# power_and_clocks.net
KiCad netlist of a schematic drawn in Altium Designer
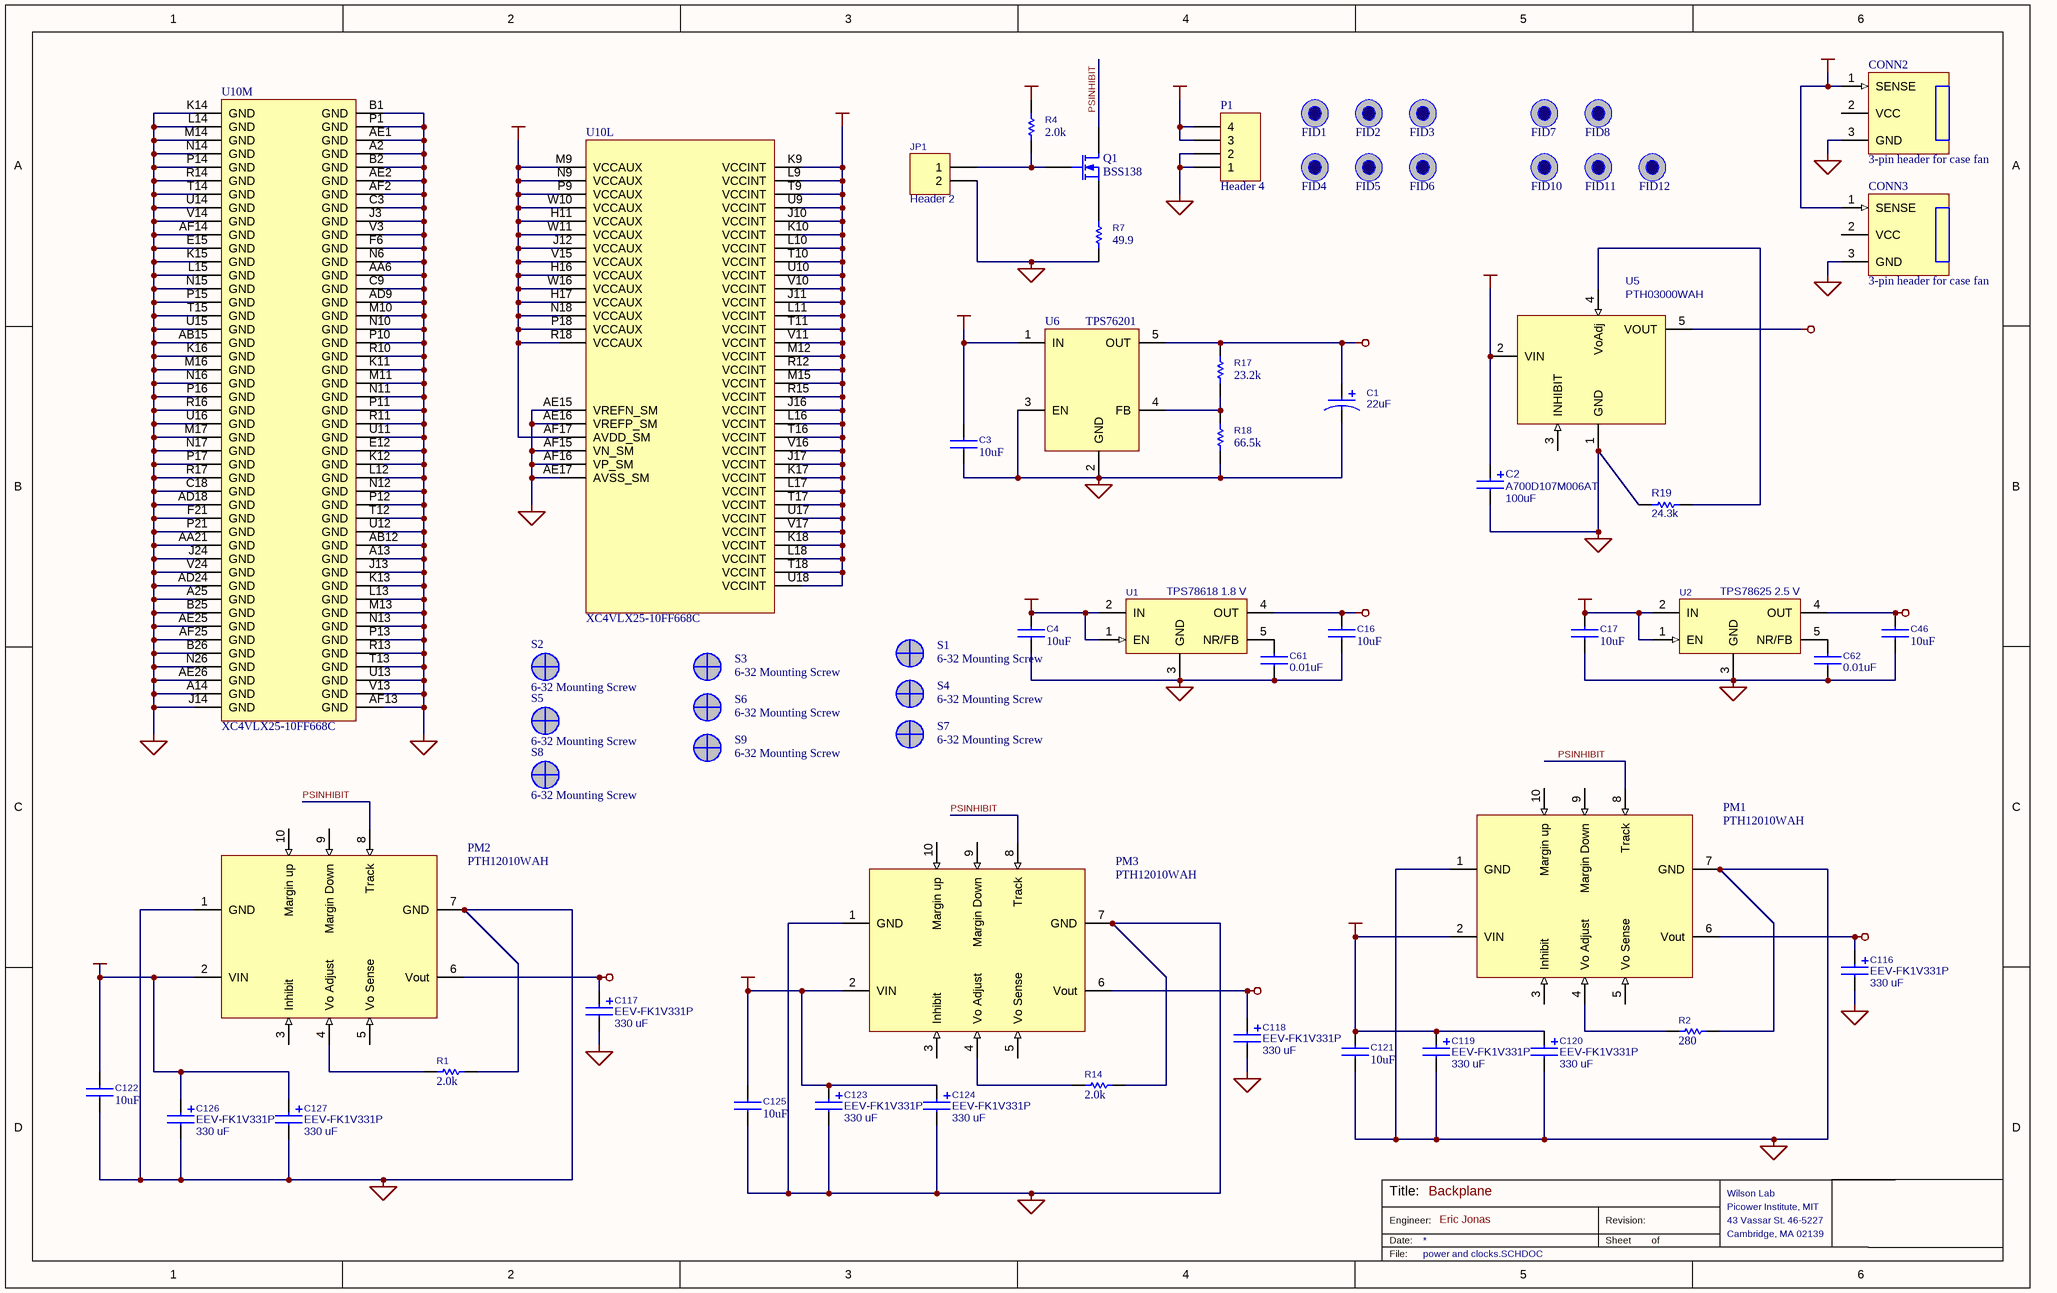
[diagram p0: power and clocks.SCHDOC]

(export (version "E")
  (design (tool "Eeschema 10.0.6"))
  (components
    (comp (ref "C1")
      (value "22uF")
      (footprint "6032")
      (description "Standard Capacitor")
      (fields (field (name "Comment") "POLCAP2"))
      (libsource (lib "parts") (part "POLCAP2"))
    )
    (comp (ref "C2")
      (value "A700D107M006AT")
      (footprint "7343")
      (description "Standard Capacitor")
      (fields (field (name "ALTIUM_VALUE") "100uF"))
      (libsource (lib "parts") (part "POLCAP"))
    )
    (comp (ref "C3")
      (value "10uF")
      (footprint "1206")
      (description "Standard Capacitor")
      (libsource (lib "parts") (part "CAPACITOR"))
    )
    (comp (ref "C4")
      (value "10uF")
      (footprint "1206")
      (description "Standard Capacitor")
      (libsource (lib "parts") (part "CAPACITOR"))
    )
    (comp (ref "C16")
      (value "10uF")
      (footprint "1206")
      (description "Standard Capacitor")
      (libsource (lib "parts") (part "CAPACITOR"))
    )
    (comp (ref "C17")
      (value "10uF")
      (footprint "1206")
      (description "Standard Capacitor")
      (libsource (lib "parts") (part "CAPACITOR"))
    )
    (comp (ref "C46")
      (value "10uF")
      (footprint "1206")
      (description "Standard Capacitor")
      (libsource (lib "parts") (part "CAPACITOR"))
    )
    (comp (ref "C61")
      (value "0.01uF")
      (footprint "0402")
      (description "Standard Capacitor")
      (fields (field (name "Comment") "CAPACITOR"))
      (libsource (lib "parts") (part "CAPACITOR"))
    )
    (comp (ref "C62")
      (value "0.01uF")
      (footprint "0402")
      (description "Standard Capacitor")
      (fields (field (name "Comment") "CAPACITOR"))
      (libsource (lib "parts") (part "CAPACITOR"))
    )
    (comp (ref "C116")
      (value "EEV-FK1V331P")
      (footprint "PanasonicG")
      (description "Standard Capacitor")
      (fields (field (name "ALTIUM_VALUE") "330 uF"))
      (libsource (lib "parts") (part "POLCAP"))
    )
    (comp (ref "C117")
      (value "EEV-FK1V331P")
      (footprint "PanasonicG")
      (description "Standard Capacitor")
      (fields (field (name "ALTIUM_VALUE") "330 uF"))
      (libsource (lib "parts") (part "POLCAP"))
    )
    (comp (ref "C118")
      (value "EEV-FK1V331P")
      (footprint "PanasonicG")
      (description "Standard Capacitor")
      (fields (field (name "ALTIUM_VALUE") "330 uF"))
      (libsource (lib "parts") (part "POLCAP"))
    )
    (comp (ref "C119")
      (value "EEV-FK1V331P")
      (footprint "PanasonicG")
      (description "Standard Capacitor")
      (fields (field (name "ALTIUM_VALUE") "330 uF"))
      (libsource (lib "parts") (part "POLCAP"))
    )
    (comp (ref "C120")
      (value "EEV-FK1V331P")
      (footprint "PanasonicG")
      (description "Standard Capacitor")
      (fields (field (name "ALTIUM_VALUE") "330 uF"))
      (libsource (lib "parts") (part "POLCAP"))
    )
    (comp (ref "C121")
      (value "10uF")
      (footprint "1206")
      (description "Standard Capacitor")
      (libsource (lib "parts") (part "CAPACITOR"))
    )
    (comp (ref "C122")
      (value "10uF")
      (footprint "1206")
      (description "Standard Capacitor")
      (libsource (lib "parts") (part "CAPACITOR"))
    )
    (comp (ref "C123")
      (value "EEV-FK1V331P")
      (footprint "PanasonicG")
      (description "Standard Capacitor")
      (fields (field (name "ALTIUM_VALUE") "330 uF"))
      (libsource (lib "parts") (part "POLCAP"))
    )
    (comp (ref "C124")
      (value "EEV-FK1V331P")
      (footprint "PanasonicG")
      (description "Standard Capacitor")
      (fields (field (name "ALTIUM_VALUE") "330 uF"))
      (libsource (lib "parts") (part "POLCAP"))
    )
    (comp (ref "C125")
      (value "10uF")
      (footprint "1206")
      (description "Standard Capacitor")
      (libsource (lib "parts") (part "CAPACITOR"))
    )
    (comp (ref "C126")
      (value "EEV-FK1V331P")
      (footprint "PanasonicG")
      (description "Standard Capacitor")
      (fields (field (name "ALTIUM_VALUE") "330 uF"))
      (libsource (lib "parts") (part "POLCAP"))
    )
    (comp (ref "C127")
      (value "EEV-FK1V331P")
      (footprint "PanasonicG")
      (description "Standard Capacitor")
      (fields (field (name "ALTIUM_VALUE") "330 uF"))
      (libsource (lib "parts") (part "POLCAP"))
    )
    (comp (ref "CONN2")
      (value "3-pin header for case fan")
      (footprint "CASEFANHDR")
      (libsource (lib "parts") (part "PCFANHEADER"))
    )
    (comp (ref "CONN3")
      (value "3-pin header for case fan")
      (footprint "CASEFANHDR")
      (libsource (lib "parts") (part "PCFANHEADER"))
    )
    (comp (ref "FID1")
      (value "FIDUCIAL")
      (footprint "FIDUCIAL")
      (description "Fiducial")
      (libsource (lib "parts") (part "FIDUCIAL"))
    )
    (comp (ref "FID2")
      (value "FIDUCIAL")
      (footprint "FIDUCIAL")
      (description "Fiducial")
      (libsource (lib "parts") (part "FIDUCIAL"))
    )
    (comp (ref "FID3")
      (value "FIDUCIAL")
      (footprint "FIDUCIAL")
      (description "Fiducial")
      (libsource (lib "parts") (part "FIDUCIAL"))
    )
    (comp (ref "FID4")
      (value "FIDUCIAL")
      (footprint "FIDUCIAL")
      (description "Fiducial")
      (libsource (lib "parts") (part "FIDUCIAL"))
    )
    (comp (ref "FID5")
      (value "FIDUCIAL")
      (footprint "FIDUCIAL")
      (description "Fiducial")
      (libsource (lib "parts") (part "FIDUCIAL"))
    )
    (comp (ref "FID6")
      (value "FIDUCIAL")
      (footprint "FIDUCIAL")
      (description "Fiducial")
      (libsource (lib "parts") (part "FIDUCIAL"))
    )
    (comp (ref "FID7")
      (value "FIDUCIAL")
      (footprint "FIDUCIAL")
      (description "Fiducial")
      (libsource (lib "parts") (part "FIDUCIAL"))
    )
    (comp (ref "FID8")
      (value "FIDUCIAL")
      (footprint "FIDUCIAL")
      (description "Fiducial")
      (libsource (lib "parts") (part "FIDUCIAL"))
    )
    (comp (ref "FID10")
      (value "FIDUCIAL")
      (footprint "FIDUCIAL")
      (description "Fiducial")
      (libsource (lib "parts") (part "FIDUCIAL"))
    )
    (comp (ref "FID11")
      (value "FIDUCIAL")
      (footprint "FIDUCIAL")
      (description "Fiducial")
      (libsource (lib "parts") (part "FIDUCIAL"))
    )
    (comp (ref "FID12")
      (value "FIDUCIAL")
      (footprint "FIDUCIAL")
      (description "Fiducial")
      (libsource (lib "parts") (part "FIDUCIAL"))
    )
    (comp (ref "JP1")
      (value "Header 2")
      (footprint "HDR1X2")
      (description "Header, 2-Pin")
      (fields (field (name "MANUFACTURER") "Generic Components") (field (name "PUBLISHER") "Altium Limited"))
      (libsource (lib "Miscellaneous Connectors") (part "Header 2"))
    )
    (comp (ref "P1")
      (value "Header 4")
      (footprint "MOLEX 39-29-9042")
      (description "Header, 4-Pin")
      (fields (field (name "PUBLISHER") "Altium Limited"))
      (libsource (lib "Miscellaneous Connectors") (part "Header 4"))
    )
    (comp (ref "PM1")
      (value "PTH12010WAH")
      (footprint "PTH12010WAH")
      (description "12A 12V Input Non-isolated wide-output adj")
      (libsource (lib "parts") (part "PTH12010W"))
    )
    (comp (ref "PM2")
      (value "PTH12010WAH")
      (footprint "PTH12010WAH")
      (description "12A 12V Input Non-isolated wide-output adj")
      (libsource (lib "parts") (part "PTH12010W"))
    )
    (comp (ref "PM3")
      (value "PTH12010WAH")
      (footprint "PTH12010WAH")
      (description "12A 12V Input Non-isolated wide-output adj")
      (libsource (lib "parts") (part "PTH12010W"))
    )
    (comp (ref "Q1") (value "BSS138") (footprint "SO-G3/D4.1") (libsource (lib "parts") (part "BSS138")))
    (comp (ref "R1")
      (value "2.0k")
      (footprint "1206")
      (description "Standard Passive Resistor")
      (fields (field (name "TOLERANCE") "1%"))
      (libsource (lib "parts") (part "RESISTOR"))
    )
    (comp (ref "R2")
      (value "280")
      (footprint "1206")
      (description "Standard Passive Resistor")
      (fields (field (name "TOLERANCE") "1%"))
      (libsource (lib "parts") (part "RESISTOR"))
    )
    (comp (ref "R4")
      (value "2.0k")
      (footprint "1206")
      (description "Standard Passive Resistor")
      (fields (field (name "TOLERANCE") "1%") (field (name "Comment") "5k"))
      (libsource (lib "parts") (part "RESISTOR"))
    )
    (comp (ref "R7")
      (value "49.9")
      (footprint "1206")
      (description "Standard Passive Resistor")
      (fields (field (name "TOLERANCE") "1%") (field (name "Comment") "50"))
      (libsource (lib "parts") (part "RESISTOR"))
    )
    (comp (ref "R14")
      (value "2.0k")
      (footprint "1206")
      (description "Standard Passive Resistor")
      (fields (field (name "TOLERANCE") "1%"))
      (libsource (lib "parts") (part "RESISTOR"))
    )
    (comp (ref "R17")
      (value "23.2k")
      (footprint "1206")
      (description "Standard Passive Resistor")
      (fields (field (name "TOLERANCE") "1%"))
      (libsource (lib "parts") (part "RESISTOR"))
    )
    (comp (ref "R18")
      (value "66.5k")
      (footprint "1206")
      (description "Standard Passive Resistor")
      (fields (field (name "TOLERANCE") "1%"))
      (libsource (lib "parts") (part "RESISTOR"))
    )
    (comp (ref "R19")
      (value "24.3k")
      (footprint "1206")
      (description "Standard Passive Resistor")
      (fields (field (name "TOLERANCE") "1%") (field (name "Comment") "RESISTOR"))
      (libsource (lib "parts") (part "RESISTOR"))
    )
    (comp (ref "S1")
      (value "6-32 Mounting Screw")
      (footprint "SCREW6-32")
      (libsource (lib "parts") (part "MNTSCREW"))
    )
    (comp (ref "S2")
      (value "6-32 Mounting Screw")
      (footprint "SCREW6-32")
      (libsource (lib "parts") (part "MNTSCREW"))
    )
    (comp (ref "S3")
      (value "6-32 Mounting Screw")
      (footprint "SCREW6-32")
      (libsource (lib "parts") (part "MNTSCREW"))
    )
    (comp (ref "S4")
      (value "6-32 Mounting Screw")
      (footprint "SCREW6-32")
      (libsource (lib "parts") (part "MNTSCREW"))
    )
    (comp (ref "S5")
      (value "6-32 Mounting Screw")
      (footprint "SCREW6-32")
      (libsource (lib "parts") (part "MNTSCREW"))
    )
    (comp (ref "S6")
      (value "6-32 Mounting Screw")
      (footprint "SCREW6-32")
      (libsource (lib "parts") (part "MNTSCREW"))
    )
    (comp (ref "S7")
      (value "6-32 Mounting Screw")
      (footprint "SCREW6-32")
      (libsource (lib "parts") (part "MNTSCREW"))
    )
    (comp (ref "S8")
      (value "6-32 Mounting Screw")
      (footprint "SCREW6-32")
      (libsource (lib "parts") (part "MNTSCREW"))
    )
    (comp (ref "S9")
      (value "6-32 Mounting Screw")
      (footprint "SCREW6-32")
      (libsource (lib "parts") (part "MNTSCREW"))
    )
    (comp (ref "U1")
      (value "TPS78618 1.8 V")
      (footprint "KTT")
      (description "TI 1.5A LDO")
      (libsource (lib "parts") (part "TPS768XX"))
    )
    (comp (ref "U2")
      (value "TPS78625 2.5 V")
      (footprint "KTT")
      (description "TI 1.5A LDO")
      (libsource (lib "parts") (part "TPS786XX"))
    )
    (comp (ref "U5") (value "PTH03000WAH") (footprint "TI EUS") (libsource (lib "parts") (part "PTH03000")))
    (comp (ref "U6")
      (value "TPS76201")
      (footprint "SO-G5/X.5")
      (description "TI 100mA LDO")
      (libsource (lib "parts") (part "TSP76201"))
    )
    (comp (ref "U10")
      (value "XC4VLX25-10FF668C")
      (footprint "Xilinx FF668")
      (description "Xilinx Virtex-4")
      (libsource (lib "parts") (part "XC4VLX25-10FF668C"))
    )
  )
  (nets
    (net (code "1") (name "+0.9VCC") (class "Default")
      (node (ref "C1") (pin "1") (pintype "passive"))
      (node (ref "R17") (pin "1") (pintype "passive"))
      (node (ref "U6") (pin "5") (pinfunction "OUT_5") (pintype "power_in"))
    )
    (net (code "2") (name "+1.2VCC") (class "Default")
      (node (ref "U10") (pin "J10") (pinfunction "VCCINT_J10") (pintype "power_in"))
      (node (ref "U10") (pin "J11") (pinfunction "VCCINT_J11") (pintype "power_in"))
      (node (ref "U10") (pin "J16") (pinfunction "VCCINT_J16") (pintype "power_in"))
      (node (ref "U10") (pin "J17") (pinfunction "VCCINT_J17") (pintype "power_in"))
      (node (ref "U10") (pin "K10") (pinfunction "VCCINT_K10") (pintype "power_in"))
      (node (ref "U10") (pin "K17") (pinfunction "VCCINT_K17") (pintype "power_in"))
      (node (ref "U10") (pin "K18") (pinfunction "VCCINT_K18") (pintype "power_in"))
      (node (ref "U10") (pin "K9") (pinfunction "VCCINT_K9") (pintype "power_in"))
      (node (ref "U10") (pin "L10") (pinfunction "VCCINT_L10") (pintype "power_in"))
      (node (ref "U10") (pin "L11") (pinfunction "VCCINT_L11") (pintype "power_in"))
      (node (ref "U10") (pin "L16") (pinfunction "VCCINT_L16") (pintype "power_in"))
      (node (ref "U10") (pin "L17") (pinfunction "VCCINT_L17") (pintype "power_in"))
      (node (ref "U10") (pin "L18") (pinfunction "VCCINT_L18") (pintype "power_in"))
      (node (ref "U10") (pin "L9") (pinfunction "VCCINT_L9") (pintype "power_in"))
      (node (ref "U10") (pin "M12") (pinfunction "VCCINT_M12") (pintype "power_in"))
      (node (ref "U10") (pin "M15") (pinfunction "VCCINT_M15") (pintype "power_in"))
      (node (ref "U10") (pin "R12") (pinfunction "VCCINT_R12") (pintype "power_in"))
      (node (ref "U10") (pin "R15") (pinfunction "VCCINT_R15") (pintype "power_in"))
      (node (ref "U10") (pin "T10") (pinfunction "VCCINT_T10") (pintype "power_in"))
      (node (ref "U10") (pin "T11") (pinfunction "VCCINT_T11") (pintype "power_in"))
      (node (ref "U10") (pin "T16") (pinfunction "VCCINT_T16") (pintype "power_in"))
      (node (ref "U10") (pin "T17") (pinfunction "VCCINT_T17") (pintype "power_in"))
      (node (ref "U10") (pin "T18") (pinfunction "VCCINT_T18") (pintype "power_in"))
      (node (ref "U10") (pin "T9") (pinfunction "VCCINT_T9") (pintype "power_in"))
      (node (ref "U10") (pin "U10") (pinfunction "VCCINT_U10") (pintype "power_in"))
      (node (ref "U10") (pin "U17") (pinfunction "VCCINT_U17") (pintype "power_in"))
      (node (ref "U10") (pin "U18") (pinfunction "VCCINT_U18") (pintype "power_in"))
      (node (ref "U10") (pin "U9") (pinfunction "VCCINT_U9") (pintype "power_in"))
      (node (ref "U10") (pin "V10") (pinfunction "VCCINT_V10") (pintype "power_in"))
      (node (ref "U10") (pin "V11") (pinfunction "VCCINT_V11") (pintype "power_in"))
      (node (ref "U10") (pin "V16") (pinfunction "VCCINT_V16") (pintype "power_in"))
      (node (ref "U10") (pin "V17") (pinfunction "VCCINT_V17") (pintype "power_in"))
      (node (ref "U5") (pin "5") (pinfunction "VOUT_5") (pintype "power_in"))
    )
    (net (code "3") (name "+1.8VCC") (class "Default")
      (node (ref "C16") (pin "2") (pintype "passive"))
      (node (ref "U1") (pin "4") (pinfunction "OUT_4") (pintype "power_in"))
    )
    (net (code "4") (name "+2.5VCC") (class "Default")
      (node (ref "C46") (pin "2") (pintype "passive"))
      (node (ref "U10") (pin "AF17") (pinfunction "AVDD_SM_AF17") (pintype "power_in"))
      (node (ref "U10") (pin "H11") (pinfunction "VCCAUX_H11") (pintype "power_in"))
      (node (ref "U10") (pin "H16") (pinfunction "VCCAUX_H16") (pintype "power_in"))
      (node (ref "U10") (pin "H17") (pinfunction "VCCAUX_H17") (pintype "power_in"))
      (node (ref "U10") (pin "J12") (pinfunction "VCCAUX_J12") (pintype "power_in"))
      (node (ref "U10") (pin "M9") (pinfunction "VCCAUX_M9") (pintype "power_in"))
      (node (ref "U10") (pin "N18") (pinfunction "VCCAUX_N18") (pintype "power_in"))
      (node (ref "U10") (pin "N9") (pinfunction "VCCAUX_N9") (pintype "power_in"))
      (node (ref "U10") (pin "P18") (pinfunction "VCCAUX_P18") (pintype "power_in"))
      (node (ref "U10") (pin "P9") (pinfunction "VCCAUX_P9") (pintype "power_in"))
      (node (ref "U10") (pin "R18") (pinfunction "VCCAUX_R18") (pintype "power_in"))
      (node (ref "U10") (pin "V15") (pinfunction "VCCAUX_V15") (pintype "power_in"))
      (node (ref "U10") (pin "W10") (pinfunction "VCCAUX_W10") (pintype "power_in"))
      (node (ref "U10") (pin "W11") (pinfunction "VCCAUX_W11") (pintype "power_in"))
      (node (ref "U10") (pin "W16") (pinfunction "VCCAUX_W16") (pintype "power_in"))
      (node (ref "U2") (pin "4") (pinfunction "OUT_4") (pintype "power_in"))
    )
    (net (code "5") (name "+5VCC") (class "Default")
      (node (ref "C116") (pin "1") (pintype "passive"))
      (node (ref "PM1") (pin "6") (pinfunction "Vout_6") (pintype "power_in"))
    )
    (net (code "6") (name "+12VCC") (class "Default")
      (node (ref "C119") (pin "1") (pintype "passive"))
      (node (ref "C120") (pin "1") (pintype "passive"))
      (node (ref "C121") (pin "2") (pintype "passive"))
      (node (ref "C122") (pin "2") (pintype "passive"))
      (node (ref "C123") (pin "1") (pintype "passive"))
      (node (ref "C124") (pin "1") (pintype "passive"))
      (node (ref "C125") (pin "2") (pintype "passive"))
      (node (ref "C126") (pin "1") (pintype "passive"))
      (node (ref "C127") (pin "1") (pintype "passive"))
      (node (ref "CONN2") (pin "1") (pinfunction "SENSE_1") (pintype "input"))
      (node (ref "CONN3") (pin "1") (pinfunction "SENSE_1") (pintype "input"))
      (node (ref "P1") (pin "3") (pinfunction "3_3") (pintype "passive"))
      (node (ref "P1") (pin "4") (pinfunction "4_4") (pintype "passive"))
      (node (ref "PM1") (pin "2") (pinfunction "VIN_2") (pintype "power_in"))
      (node (ref "PM2") (pin "2") (pinfunction "VIN_2") (pintype "power_in"))
      (node (ref "PM3") (pin "2") (pinfunction "VIN_2") (pintype "power_in"))
    )
    (net (code "7") (name "/PSINHIBIT") (class "Default")
      (node (ref "PM1") (pin "8") (pinfunction "Track_8") (pintype "input"))
      (node (ref "PM2") (pin "8") (pinfunction "Track_8") (pintype "input"))
      (node (ref "PM3") (pin "8") (pinfunction "Track_8") (pintype "input"))
      (node (ref "Q1") (pin "1") (pinfunction "D_1") (pintype "passive"))
    )
    (net (code "8") (name "GND") (class "Default")
      (node (ref "C1") (pin "2") (pintype "passive"))
      (node (ref "C116") (pin "2") (pintype "passive"))
      (node (ref "C117") (pin "2") (pintype "passive"))
      (node (ref "C118") (pin "2") (pintype "passive"))
      (node (ref "C119") (pin "2") (pintype "passive"))
      (node (ref "C120") (pin "2") (pintype "passive"))
      (node (ref "C121") (pin "1") (pintype "passive"))
      (node (ref "C122") (pin "1") (pintype "passive"))
      (node (ref "C123") (pin "2") (pintype "passive"))
      (node (ref "C124") (pin "2") (pintype "passive"))
      (node (ref "C125") (pin "1") (pintype "passive"))
      (node (ref "C126") (pin "2") (pintype "passive"))
      (node (ref "C127") (pin "2") (pintype "passive"))
      (node (ref "C16") (pin "1") (pintype "passive"))
      (node (ref "C17") (pin "1") (pintype "passive"))
      (node (ref "C2") (pin "2") (pintype "passive"))
      (node (ref "C3") (pin "1") (pintype "passive"))
      (node (ref "C4") (pin "1") (pintype "passive"))
      (node (ref "C46") (pin "1") (pintype "passive"))
      (node (ref "C61") (pin "2") (pintype "passive"))
      (node (ref "C62") (pin "2") (pintype "passive"))
      (node (ref "CONN2") (pin "3") (pinfunction "GND_3") (pintype "power_in"))
      (node (ref "CONN3") (pin "3") (pinfunction "GND_3") (pintype "power_in"))
      (node (ref "JP1") (pin "2") (pinfunction "2_2") (pintype "passive"))
      (node (ref "P1") (pin "1") (pinfunction "1_1") (pintype "passive"))
      (node (ref "P1") (pin "2") (pinfunction "2_2") (pintype "passive"))
      (node (ref "PM1") (pin "1") (pinfunction "GND_1") (pintype "power_in"))
      (node (ref "PM1") (pin "7") (pinfunction "GND_7") (pintype "power_in"))
      (node (ref "PM2") (pin "1") (pinfunction "GND_1") (pintype "power_in"))
      (node (ref "PM2") (pin "7") (pinfunction "GND_7") (pintype "power_in"))
      (node (ref "PM3") (pin "1") (pinfunction "GND_1") (pintype "power_in"))
      (node (ref "PM3") (pin "7") (pinfunction "GND_7") (pintype "power_in"))
      (node (ref "R1") (pin "1") (pintype "passive"))
      (node (ref "R14") (pin "1") (pintype "passive"))
      (node (ref "R18") (pin "2") (pintype "passive"))
      (node (ref "R19") (pin "2") (pintype "passive"))
      (node (ref "R2") (pin "1") (pintype "passive"))
      (node (ref "R7") (pin "2") (pintype "passive"))
      (node (ref "U1") (pin "3") (pinfunction "GND_3") (pintype "power_in"))
      (node (ref "U10") (pin "A13") (pinfunction "GND_A13") (pintype "power_in"))
      (node (ref "U10") (pin "A14") (pinfunction "GND_A14") (pintype "power_in"))
      (node (ref "U10") (pin "A2") (pinfunction "GND_A2") (pintype "power_in"))
      (node (ref "U10") (pin "A25") (pinfunction "GND_A25") (pintype "power_in"))
      (node (ref "U10") (pin "AA21") (pinfunction "GND_AA21") (pintype "power_in"))
      (node (ref "U10") (pin "AA6") (pinfunction "GND_AA6") (pintype "power_in"))
      (node (ref "U10") (pin "AB12") (pinfunction "GND_AB12") (pintype "power_in"))
      (node (ref "U10") (pin "AB15") (pinfunction "GND_AB15") (pintype "power_in"))
      (node (ref "U10") (pin "AD18") (pinfunction "GND_AD18") (pintype "power_in"))
      (node (ref "U10") (pin "AD24") (pinfunction "GND_AD24") (pintype "power_in"))
      (node (ref "U10") (pin "AD9") (pinfunction "GND_AD9") (pintype "power_in"))
      (node (ref "U10") (pin "AE1") (pinfunction "GND_AE1") (pintype "power_in"))
      (node (ref "U10") (pin "AE15") (pinfunction "VREFN_SM_AE15") (pintype "power_in"))
      (node (ref "U10") (pin "AE16") (pinfunction "VREFP_SM_AE16") (pintype "power_in"))
      (node (ref "U10") (pin "AE17") (pinfunction "AVSS_SM_AE17") (pintype "power_in"))
      (node (ref "U10") (pin "AE2") (pinfunction "GND_AE2") (pintype "power_in"))
      (node (ref "U10") (pin "AE25") (pinfunction "GND_AE25") (pintype "power_in"))
      (node (ref "U10") (pin "AE26") (pinfunction "GND_AE26") (pintype "power_in"))
      (node (ref "U10") (pin "AF13") (pinfunction "GND_AF13") (pintype "power_in"))
      (node (ref "U10") (pin "AF14") (pinfunction "GND_AF14") (pintype "power_in"))
      (node (ref "U10") (pin "AF15") (pinfunction "VN_SM_AF15") (pintype "power_in"))
      (node (ref "U10") (pin "AF16") (pinfunction "VP_SM_AF16") (pintype "power_in"))
      (node (ref "U10") (pin "AF2") (pinfunction "GND_AF2") (pintype "power_in"))
      (node (ref "U10") (pin "AF25") (pinfunction "GND_AF25") (pintype "power_in"))
      (node (ref "U10") (pin "B1") (pinfunction "GND_B1") (pintype "power_in"))
      (node (ref "U10") (pin "B2") (pinfunction "GND_B2") (pintype "power_in"))
      (node (ref "U10") (pin "B25") (pinfunction "GND_B25") (pintype "power_in"))
      (node (ref "U10") (pin "B26") (pinfunction "GND_B26") (pintype "power_in"))
      (node (ref "U10") (pin "C18") (pinfunction "GND_C18") (pintype "power_in"))
      (node (ref "U10") (pin "C3") (pinfunction "GND_C3") (pintype "power_in"))
      (node (ref "U10") (pin "C9") (pinfunction "GND_C9") (pintype "power_in"))
      (node (ref "U10") (pin "E12") (pinfunction "GND_E12") (pintype "power_in"))
      (node (ref "U10") (pin "E15") (pinfunction "GND_E15") (pintype "power_in"))
      (node (ref "U10") (pin "F21") (pinfunction "GND_F21") (pintype "power_in"))
      (node (ref "U10") (pin "F6") (pinfunction "GND_F6") (pintype "power_in"))
      (node (ref "U10") (pin "J13") (pinfunction "GND_J13") (pintype "power_in"))
      (node (ref "U10") (pin "J14") (pinfunction "GND_J14") (pintype "power_in"))
      (node (ref "U10") (pin "J24") (pinfunction "GND_J24") (pintype "power_in"))
      (node (ref "U10") (pin "J3") (pinfunction "GND_J3") (pintype "power_in"))
      (node (ref "U10") (pin "K11") (pinfunction "GND_K11") (pintype "power_in"))
      (node (ref "U10") (pin "K12") (pinfunction "GND_K12") (pintype "power_in"))
      (node (ref "U10") (pin "K13") (pinfunction "GND_K13") (pintype "power_in"))
      (node (ref "U10") (pin "K14") (pinfunction "GND_K14") (pintype "power_in"))
      (node (ref "U10") (pin "K15") (pinfunction "GND_K15") (pintype "power_in"))
      (node (ref "U10") (pin "K16") (pinfunction "GND_K16") (pintype "power_in"))
      (node (ref "U10") (pin "L12") (pinfunction "GND_L12") (pintype "power_in"))
      (node (ref "U10") (pin "L13") (pinfunction "GND_L13") (pintype "power_in"))
      (node (ref "U10") (pin "L14") (pinfunction "GND_L14") (pintype "power_in"))
      (node (ref "U10") (pin "L15") (pinfunction "GND_L15") (pintype "power_in"))
      (node (ref "U10") (pin "M10") (pinfunction "GND_M10") (pintype "power_in"))
      (node (ref "U10") (pin "M11") (pinfunction "GND_M11") (pintype "power_in"))
      (node (ref "U10") (pin "M13") (pinfunction "GND_M13") (pintype "power_in"))
      (node (ref "U10") (pin "M14") (pinfunction "GND_M14") (pintype "power_in"))
      (node (ref "U10") (pin "M16") (pinfunction "GND_M16") (pintype "power_in"))
      (node (ref "U10") (pin "M17") (pinfunction "GND_M17") (pintype "power_in"))
      (node (ref "U10") (pin "N10") (pinfunction "GND_N10") (pintype "power_in"))
      (node (ref "U10") (pin "N11") (pinfunction "GND_N11") (pintype "power_in"))
      (node (ref "U10") (pin "N12") (pinfunction "GND_N12") (pintype "power_in"))
      (node (ref "U10") (pin "N13") (pinfunction "GND_N13") (pintype "power_in"))
      (node (ref "U10") (pin "N14") (pinfunction "GND_N14") (pintype "power_in"))
      (node (ref "U10") (pin "N15") (pinfunction "GND_N15") (pintype "power_in"))
      (node (ref "U10") (pin "N16") (pinfunction "GND_N16") (pintype "power_in"))
      (node (ref "U10") (pin "N17") (pinfunction "GND_N17") (pintype "power_in"))
      (node (ref "U10") (pin "N26") (pinfunction "GND_N26") (pintype "power_in"))
      (node (ref "U10") (pin "N6") (pinfunction "GND_N6") (pintype "power_in"))
      (node (ref "U10") (pin "P1") (pinfunction "GND_P1") (pintype "power_in"))
      (node (ref "U10") (pin "P10") (pinfunction "GND_P10") (pintype "power_in"))
      (node (ref "U10") (pin "P11") (pinfunction "GND_P11") (pintype "power_in"))
      (node (ref "U10") (pin "P12") (pinfunction "GND_P12") (pintype "power_in"))
      (node (ref "U10") (pin "P13") (pinfunction "GND_P13") (pintype "power_in"))
      (node (ref "U10") (pin "P14") (pinfunction "GND_P14") (pintype "power_in"))
      (node (ref "U10") (pin "P15") (pinfunction "GND_P15") (pintype "power_in"))
      (node (ref "U10") (pin "P16") (pinfunction "GND_P16") (pintype "power_in"))
      (node (ref "U10") (pin "P17") (pinfunction "GND_P17") (pintype "power_in"))
      (node (ref "U10") (pin "P21") (pinfunction "GND_P21") (pintype "power_in"))
      (node (ref "U10") (pin "R10") (pinfunction "GND_R10") (pintype "power_in"))
      (node (ref "U10") (pin "R11") (pinfunction "GND_R11") (pintype "power_in"))
      (node (ref "U10") (pin "R13") (pinfunction "GND_R13") (pintype "power_in"))
      (node (ref "U10") (pin "R14") (pinfunction "GND_R14") (pintype "power_in"))
      (node (ref "U10") (pin "R16") (pinfunction "GND_R16") (pintype "power_in"))
      (node (ref "U10") (pin "R17") (pinfunction "GND_R17") (pintype "power_in"))
      (node (ref "U10") (pin "T12") (pinfunction "GND_T12") (pintype "power_in"))
      (node (ref "U10") (pin "T13") (pinfunction "GND_T13") (pintype "power_in"))
      (node (ref "U10") (pin "T14") (pinfunction "GND_T14") (pintype "power_in"))
      (node (ref "U10") (pin "T15") (pinfunction "GND_T15") (pintype "power_in"))
      (node (ref "U10") (pin "U11") (pinfunction "GND_U11") (pintype "power_in"))
      (node (ref "U10") (pin "U12") (pinfunction "GND_U12") (pintype "power_in"))
      (node (ref "U10") (pin "U13") (pinfunction "GND_U13") (pintype "power_in"))
      (node (ref "U10") (pin "U14") (pinfunction "GND_U14") (pintype "power_in"))
      (node (ref "U10") (pin "U15") (pinfunction "GND_U15") (pintype "power_in"))
      (node (ref "U10") (pin "U16") (pinfunction "GND_U16") (pintype "power_in"))
      (node (ref "U10") (pin "V13") (pinfunction "GND_V13") (pintype "power_in"))
      (node (ref "U10") (pin "V14") (pinfunction "GND_V14") (pintype "power_in"))
      (node (ref "U10") (pin "V24") (pinfunction "GND_V24") (pintype "power_in"))
      (node (ref "U10") (pin "V3") (pinfunction "GND_V3") (pintype "power_in"))
      (node (ref "U2") (pin "3") (pinfunction "GND_3") (pintype "power_in"))
      (node (ref "U5") (pin "1") (pinfunction "GND_1") (pintype "power_in"))
      (node (ref "U6") (pin "2") (pinfunction "GND_2") (pintype "power_in"))
      (node (ref "U6") (pin "3") (pinfunction "EN_3") (pintype "power_in"))
    )
    (net (code "9") (name "Net-(PM1-Vo_Adjust)") (class "Default")
      (node (ref "PM1") (pin "4") (pinfunction "Vo_Adjust_4") (pintype "input"))
      (node (ref "R2") (pin "2") (pintype "passive"))
    )
    (net (code "10") (name "Net-(PM2-Vo_Adjust)") (class "Default")
      (node (ref "PM2") (pin "4") (pinfunction "Vo_Adjust_4") (pintype "input"))
      (node (ref "R1") (pin "2") (pintype "passive"))
    )
    (net (code "11") (name "Net-(PM3-Vo_Adjust)") (class "Default")
      (node (ref "PM3") (pin "4") (pinfunction "Vo_Adjust_4") (pintype "input"))
      (node (ref "R14") (pin "2") (pintype "passive"))
    )
    (net (code "12") (name "Net-(Q1-G)") (class "Default")
      (node (ref "JP1") (pin "1") (pinfunction "1_1") (pintype "passive"))
      (node (ref "Q1") (pin "2") (pinfunction "G_2") (pintype "passive"))
      (node (ref "R4") (pin "2") (pintype "passive"))
    )
    (net (code "13") (name "Net-(Q1-S)") (class "Default")
      (node (ref "Q1") (pin "3") (pinfunction "S_3") (pintype "passive"))
      (node (ref "R7") (pin "1") (pintype "passive"))
    )
    (net (code "14") (name "Net-(U1-NR{slash}FB)") (class "Default")
      (node (ref "C61") (pin "1") (pintype "passive"))
      (node (ref "U1") (pin "5") (pinfunction "NR/FB_5") (pintype "power_in"))
    )
    (net (code "15") (name "Net-(U2-NR{slash}FB)") (class "Default")
      (node (ref "C62") (pin "1") (pintype "passive"))
      (node (ref "U2") (pin "5") (pinfunction "NR/FB_5") (pintype "power_in"))
    )
    (net (code "16") (name "Net-(U5-VoAdj)") (class "Default")
      (node (ref "R19") (pin "1") (pintype "passive"))
      (node (ref "U5") (pin "4") (pinfunction "VoAdj_4") (pintype "input"))
    )
    (net (code "17") (name "Net-(U6-FB)") (class "Default")
      (node (ref "R17") (pin "2") (pintype "passive"))
      (node (ref "R18") (pin "1") (pintype "passive"))
      (node (ref "U6") (pin "4") (pinfunction "FB_4") (pintype "power_in"))
    )
    (net (code "18") (name "VCC") (class "Default")
      (node (ref "C117") (pin "1") (pintype "passive"))
      (node (ref "C17") (pin "2") (pintype "passive"))
      (node (ref "C2") (pin "1") (pintype "passive"))
      (node (ref "C3") (pin "2") (pintype "passive"))
      (node (ref "C4") (pin "2") (pintype "passive"))
      (node (ref "PM2") (pin "6") (pinfunction "Vout_6") (pintype "power_in"))
      (node (ref "R4") (pin "1") (pintype "passive"))
      (node (ref "U1") (pin "1") (pinfunction "EN_1") (pintype "input"))
      (node (ref "U1") (pin "2") (pinfunction "IN_2") (pintype "power_in"))
      (node (ref "U2") (pin "1") (pinfunction "EN_1") (pintype "input"))
      (node (ref "U2") (pin "2") (pinfunction "IN_2") (pintype "power_in"))
      (node (ref "U5") (pin "2") (pinfunction "VIN_2") (pintype "power_in"))
      (node (ref "U6") (pin "1") (pinfunction "IN_1") (pintype "power_in"))
    )
    (net (code "19") (name "VCC2") (class "Default")
      (node (ref "C118") (pin "1") (pintype "passive"))
      (node (ref "PM3") (pin "6") (pinfunction "Vout_6") (pintype "power_in"))
    )
    (net (code "20") (name "unconnected-(CONN2-VCC-Pad2)") (class "Default")
      (node (ref "CONN2") (pin "2") (pinfunction "VCC_2") (pintype "power_in"))
    )
    (net (code "21") (name "unconnected-(CONN3-VCC-Pad2)") (class "Default")
      (node (ref "CONN3") (pin "2") (pinfunction "VCC_2") (pintype "power_in"))
    )
    (net (code "22") (name "unconnected-(PM1-Inhibit-Pad3)") (class "Default")
      (node (ref "PM1") (pin "3") (pinfunction "Inhibit_3") (pintype "input"))
    )
    (net (code "23") (name "unconnected-(PM1-Margin_Down-Pad9)") (class "Default")
      (node (ref "PM1") (pin "9") (pinfunction "Margin_Down_9") (pintype "input"))
    )
    (net (code "24") (name "unconnected-(PM1-Margin_up-Pad10)") (class "Default")
      (node (ref "PM1") (pin "10") (pinfunction "Margin_up_10") (pintype "input"))
    )
    (net (code "25") (name "unconnected-(PM1-Vo_Sense-Pad5)") (class "Default")
      (node (ref "PM1") (pin "5") (pinfunction "Vo_Sense_5") (pintype "input"))
    )
    (net (code "26") (name "unconnected-(PM2-Inhibit-Pad3)") (class "Default")
      (node (ref "PM2") (pin "3") (pinfunction "Inhibit_3") (pintype "input"))
    )
    (net (code "27") (name "unconnected-(PM2-Margin_Down-Pad9)") (class "Default")
      (node (ref "PM2") (pin "9") (pinfunction "Margin_Down_9") (pintype "input"))
    )
    (net (code "28") (name "unconnected-(PM2-Margin_up-Pad10)") (class "Default")
      (node (ref "PM2") (pin "10") (pinfunction "Margin_up_10") (pintype "input"))
    )
    (net (code "29") (name "unconnected-(PM2-Vo_Sense-Pad5)") (class "Default")
      (node (ref "PM2") (pin "5") (pinfunction "Vo_Sense_5") (pintype "input"))
    )
    (net (code "30") (name "unconnected-(PM3-Inhibit-Pad3)") (class "Default")
      (node (ref "PM3") (pin "3") (pinfunction "Inhibit_3") (pintype "input"))
    )
    (net (code "31") (name "unconnected-(PM3-Margin_Down-Pad9)") (class "Default")
      (node (ref "PM3") (pin "9") (pinfunction "Margin_Down_9") (pintype "input"))
    )
    (net (code "32") (name "unconnected-(PM3-Margin_up-Pad10)") (class "Default")
      (node (ref "PM3") (pin "10") (pinfunction "Margin_up_10") (pintype "input"))
    )
    (net (code "33") (name "unconnected-(PM3-Vo_Sense-Pad5)") (class "Default")
      (node (ref "PM3") (pin "5") (pinfunction "Vo_Sense_5") (pintype "input"))
    )
    (net (code "34") (name "unconnected-(U5-INHIBIT-Pad3)") (class "Default")
      (node (ref "U5") (pin "3") (pinfunction "INHIBIT_3") (pintype "input"))
    )
  )
)
